# tiller.net
KiCad netlist of a schematic drawn in EAGLE
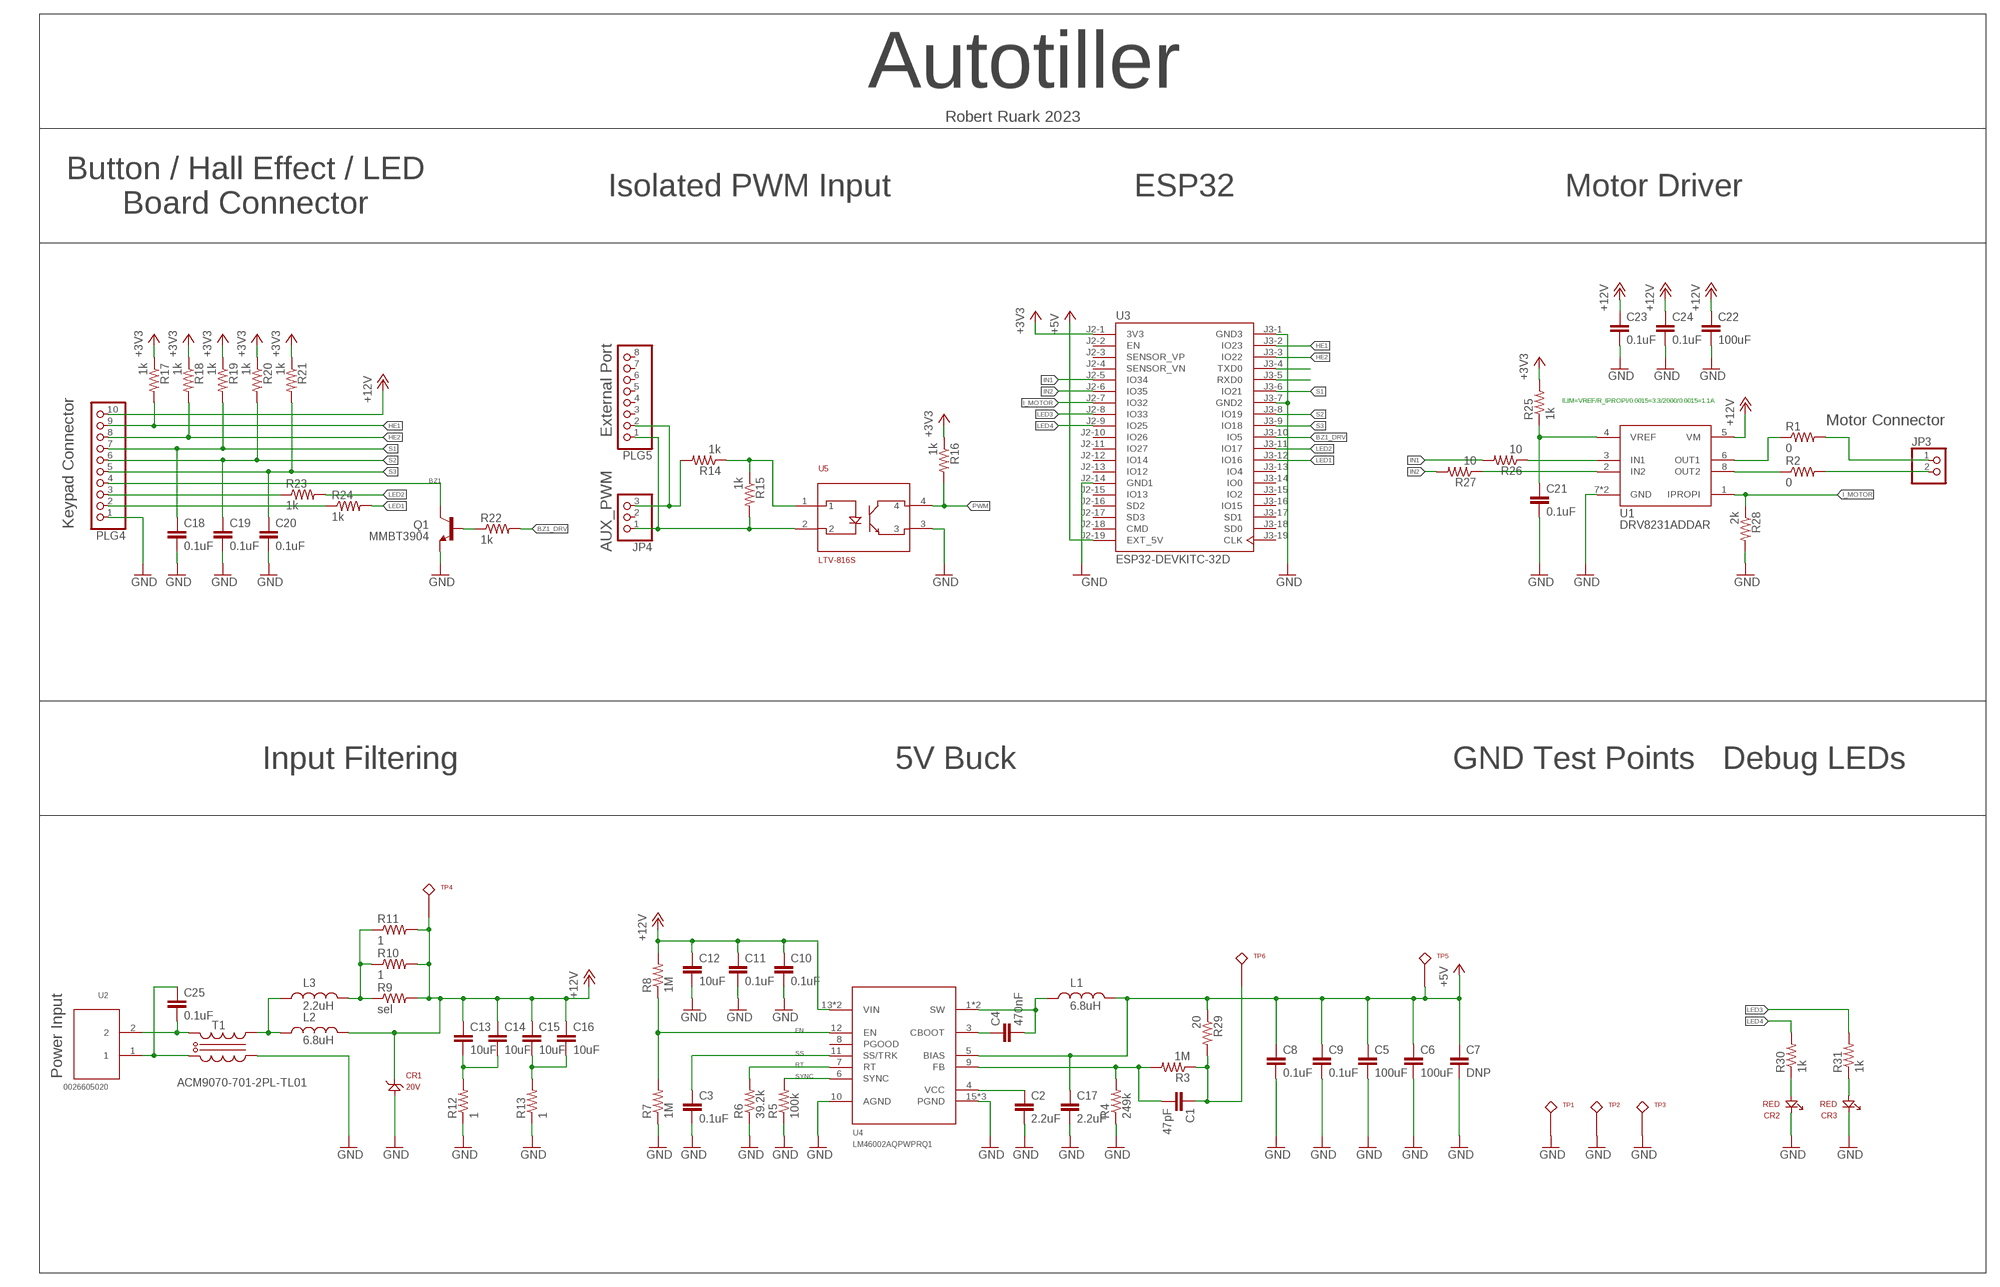
[diagram p0: schematic, sheet 1]

(export (version "E")
  (design (tool "Eeschema 10.0.6"))
  (components
    (comp (ref "C1")
      (value "47pF")
      (footprint "eagle-import:0603")
      (libsource (lib "eagle-import") (part "0603_CAPACITOR"))
    )
    (comp (ref "C2")
      (value "2.2uF")
      (footprint "eagle-import:0805")
      (libsource (lib "eagle-import") (part "0805_CAPACITOR"))
    )
    (comp (ref "C3")
      (value "0.1uF")
      (footprint "eagle-import:0603")
      (libsource (lib "eagle-import") (part "0603_CAPACITOR"))
    )
    (comp (ref "C4")
      (value "470nF")
      (footprint "eagle-import:0805")
      (libsource (lib "eagle-import") (part "0805_CAPACITOR"))
    )
    (comp (ref "C5")
      (value "100uF")
      (footprint "eagle-import:1210")
      (libsource (lib "eagle-import") (part "1210_CAPACITOR"))
    )
    (comp (ref "C6")
      (value "100uF")
      (footprint "eagle-import:1210")
      (libsource (lib "eagle-import") (part "1210_CAPACITOR"))
    )
    (comp (ref "C7")
      (value "DNP")
      (footprint "eagle-import:1210")
      (libsource (lib "eagle-import") (part "1210_CAPACITOR"))
    )
    (comp (ref "C8")
      (value "0.1uF")
      (footprint "eagle-import:0603")
      (libsource (lib "eagle-import") (part "0603_CAPACITOR"))
    )
    (comp (ref "C9")
      (value "0.1uF")
      (footprint "eagle-import:0603")
      (libsource (lib "eagle-import") (part "0603_CAPACITOR"))
    )
    (comp (ref "C10")
      (value "0.1uF")
      (footprint "eagle-import:0603")
      (libsource (lib "eagle-import") (part "0603_CAPACITOR"))
    )
    (comp (ref "C11")
      (value "0.1uF")
      (footprint "eagle-import:0603")
      (libsource (lib "eagle-import") (part "0603_CAPACITOR"))
    )
    (comp (ref "C12")
      (value "10uF")
      (footprint "eagle-import:1210")
      (libsource (lib "eagle-import") (part "1210_CAPACITOR"))
    )
    (comp (ref "C13")
      (value "10uF")
      (footprint "eagle-import:1210")
      (libsource (lib "eagle-import") (part "1210_CAPACITOR"))
    )
    (comp (ref "C14")
      (value "10uF")
      (footprint "eagle-import:1210")
      (libsource (lib "eagle-import") (part "1210_CAPACITOR"))
    )
    (comp (ref "C15")
      (value "10uF")
      (footprint "eagle-import:1210")
      (libsource (lib "eagle-import") (part "1210_CAPACITOR"))
    )
    (comp (ref "C16")
      (value "10uF")
      (footprint "eagle-import:1210")
      (libsource (lib "eagle-import") (part "1210_CAPACITOR"))
    )
    (comp (ref "C17")
      (value "2.2uF")
      (footprint "eagle-import:0805")
      (libsource (lib "eagle-import") (part "0805_CAPACITOR"))
    )
    (comp (ref "C18")
      (value "0.1uF")
      (footprint "eagle-import:0603")
      (libsource (lib "eagle-import") (part "0603_CAPACITOR"))
    )
    (comp (ref "C19")
      (value "0.1uF")
      (footprint "eagle-import:0603")
      (libsource (lib "eagle-import") (part "0603_CAPACITOR"))
    )
    (comp (ref "C20")
      (value "0.1uF")
      (footprint "eagle-import:0603")
      (libsource (lib "eagle-import") (part "0603_CAPACITOR"))
    )
    (comp (ref "C21")
      (value "0.1uF")
      (footprint "eagle-import:0603")
      (libsource (lib "eagle-import") (part "0603_CAPACITOR"))
    )
    (comp (ref "C22")
      (value "100uF")
      (footprint "eagle-import:1210")
      (libsource (lib "eagle-import") (part "1210_CAPACITOR"))
    )
    (comp (ref "C23")
      (value "0.1uF")
      (footprint "eagle-import:0603")
      (libsource (lib "eagle-import") (part "0603_CAPACITOR"))
    )
    (comp (ref "C24")
      (value "0.1uF")
      (footprint "eagle-import:0603")
      (libsource (lib "eagle-import") (part "0603_CAPACITOR"))
    )
    (comp (ref "C25")
      (value "0.1uF")
      (footprint "eagle-import:0603")
      (libsource (lib "eagle-import") (part "0603_CAPACITOR"))
    )
    (comp (ref "CR1")
      (value "20V")
      (footprint "eagle-import:DO-214AC")
      (fields (field (name "PARTNO") "732-SMAJ20ACT-ND"))
      (libsource (lib "eagle-import") (part "SMAJ20A"))
    )
    (comp (ref "CR2")
      (value "RED")
      (footprint "eagle-import:0603_DIODE")
      (fields (field (name "PARTNO") "732-4978-1-ND"))
      (libsource (lib "eagle-import") (part "150060RS75000"))
    )
    (comp (ref "CR3")
      (value "RED")
      (footprint "eagle-import:0603_DIODE")
      (fields (field (name "PARTNO") "732-4978-1-ND"))
      (libsource (lib "eagle-import") (part "150060RS75000"))
    )
    (comp (ref "JP3")
      (value "PINHD-1X2/90")
      (footprint "eagle-import:1X02_90")
      (libsource (lib "eagle-import") (part "PINHD-1X2/90"))
    )
    (comp (ref "JP4")
      (value "PINHD-1X3")
      (footprint "eagle-import:1X03")
      (libsource (lib "eagle-import") (part "PINHD-1X3"))
    )
    (comp (ref "L1")
      (value "6.8uH")
      (footprint "eagle-import:NR6028")
      (fields (field (name "PARTNO") "587-2629-1-ND"))
      (libsource (lib "eagle-import") (part "NR6020T6R8N"))
    )
    (comp (ref "L2")
      (value "6.8uH")
      (footprint "eagle-import:NR6028")
      (fields (field (name "PARTNO") "587-2629-1-ND"))
      (libsource (lib "eagle-import") (part "NR6020T6R8N"))
    )
    (comp (ref "L3")
      (value "2.2uH")
      (footprint "eagle-import:NR6028")
      (fields (field (name "PARTNO") "587-2098-1-ND"))
      (libsource (lib "eagle-import") (part "NR6028T2R2N"))
    )
    (comp (ref "PLG4")
      (value "PINHD-1X10")
      (footprint "eagle-import:1X10")
      (libsource (lib "eagle-import") (part "PINHD-1X10"))
    )
    (comp (ref "PLG5")
      (value "PINHD-1X8")
      (footprint "eagle-import:1X08")
      (libsource (lib "eagle-import") (part "PINHD-1X8"))
    )
    (comp (ref "Q1")
      (value "MMBT3904")
      (footprint "eagle-import:SOT23-3_CENTERED")
      (libsource (lib "eagle-import") (part "MMBT3904-TPCENTERED"))
    )
    (comp (ref "R1")
      (value "0")
      (footprint "eagle-import:1206")
      (libsource (lib "eagle-import") (part "1206_RESISTOR"))
    )
    (comp (ref "R2")
      (value "0")
      (footprint "eagle-import:1206")
      (libsource (lib "eagle-import") (part "1206_RESISTOR"))
    )
    (comp (ref "R3")
      (value "1M")
      (footprint "eagle-import:0603")
      (libsource (lib "eagle-import") (part "0603_RESISTOR"))
    )
    (comp (ref "R4")
      (value "249k")
      (footprint "eagle-import:0603")
      (libsource (lib "eagle-import") (part "0603_RESISTOR"))
    )
    (comp (ref "R5")
      (value "100k")
      (footprint "eagle-import:0603")
      (libsource (lib "eagle-import") (part "0603_RESISTOR"))
    )
    (comp (ref "R6")
      (value "39.2k")
      (footprint "eagle-import:0603")
      (libsource (lib "eagle-import") (part "0603_RESISTOR"))
    )
    (comp (ref "R7")
      (value "1M")
      (footprint "eagle-import:0603")
      (libsource (lib "eagle-import") (part "0603_RESISTOR"))
    )
    (comp (ref "R8")
      (value "1M")
      (footprint "eagle-import:0603")
      (libsource (lib "eagle-import") (part "0603_RESISTOR"))
    )
    (comp (ref "R9")
      (value "sel")
      (footprint "eagle-import:1206")
      (libsource (lib "eagle-import") (part "1206_RESISTOR"))
    )
    (comp (ref "R10")
      (value "1")
      (footprint "eagle-import:1206")
      (libsource (lib "eagle-import") (part "1206_RESISTOR"))
    )
    (comp (ref "R11")
      (value "1")
      (footprint "eagle-import:1206")
      (libsource (lib "eagle-import") (part "1206_RESISTOR"))
    )
    (comp (ref "R12")
      (value "1")
      (footprint "eagle-import:1206")
      (libsource (lib "eagle-import") (part "1206_RESISTOR"))
    )
    (comp (ref "R13")
      (value "1")
      (footprint "eagle-import:1206")
      (libsource (lib "eagle-import") (part "1206_RESISTOR"))
    )
    (comp (ref "R14")
      (value "1k")
      (footprint "eagle-import:0603")
      (libsource (lib "eagle-import") (part "0603_RESISTOR"))
    )
    (comp (ref "R15")
      (value "1k")
      (footprint "eagle-import:0603")
      (libsource (lib "eagle-import") (part "0603_RESISTOR"))
    )
    (comp (ref "R16")
      (value "1k")
      (footprint "eagle-import:0603")
      (libsource (lib "eagle-import") (part "0603_RESISTOR"))
    )
    (comp (ref "R17")
      (value "1k")
      (footprint "eagle-import:0603")
      (libsource (lib "eagle-import") (part "0603_RESISTOR"))
    )
    (comp (ref "R18")
      (value "1k")
      (footprint "eagle-import:0603")
      (libsource (lib "eagle-import") (part "0603_RESISTOR"))
    )
    (comp (ref "R19")
      (value "1k")
      (footprint "eagle-import:0603")
      (libsource (lib "eagle-import") (part "0603_RESISTOR"))
    )
    (comp (ref "R20")
      (value "1k")
      (footprint "eagle-import:0603")
      (libsource (lib "eagle-import") (part "0603_RESISTOR"))
    )
    (comp (ref "R21")
      (value "1k")
      (footprint "eagle-import:0603")
      (libsource (lib "eagle-import") (part "0603_RESISTOR"))
    )
    (comp (ref "R22")
      (value "1k")
      (footprint "eagle-import:0603")
      (libsource (lib "eagle-import") (part "0603_RESISTOR"))
    )
    (comp (ref "R23")
      (value "1k")
      (footprint "eagle-import:0603")
      (libsource (lib "eagle-import") (part "0603_RESISTOR"))
    )
    (comp (ref "R24")
      (value "1k")
      (footprint "eagle-import:0603")
      (libsource (lib "eagle-import") (part "0603_RESISTOR"))
    )
    (comp (ref "R25")
      (value "1k")
      (footprint "eagle-import:0603")
      (libsource (lib "eagle-import") (part "0603_RESISTOR"))
    )
    (comp (ref "R26")
      (value "10")
      (footprint "eagle-import:0603")
      (libsource (lib "eagle-import") (part "0603_RESISTOR"))
    )
    (comp (ref "R27")
      (value "10")
      (footprint "eagle-import:0603")
      (libsource (lib "eagle-import") (part "0603_RESISTOR"))
    )
    (comp (ref "R28")
      (value "2k")
      (footprint "eagle-import:0603")
      (libsource (lib "eagle-import") (part "0603_RESISTOR"))
    )
    (comp (ref "R29")
      (value "20")
      (footprint "eagle-import:0603")
      (libsource (lib "eagle-import") (part "0603_RESISTOR"))
    )
    (comp (ref "R30")
      (value "1k")
      (footprint "eagle-import:0603")
      (libsource (lib "eagle-import") (part "0603_RESISTOR"))
    )
    (comp (ref "R31")
      (value "1k")
      (footprint "eagle-import:0603")
      (libsource (lib "eagle-import") (part "0603_RESISTOR"))
    )
    (comp (ref "T1")
      (value "ACM9070-701-2PL-TL01")
      (footprint "eagle-import:ACM9070")
      (fields (field (name "PARTNO") "445-2216-1-ND"))
      (libsource (lib "eagle-import") (part "ACM9070-701-2PL-TL01"))
    )
    (comp (ref "TP1")
      (value "5011")
      (footprint "eagle-import:5010")
      (fields (field (name "PARTNO") "36-5011-ND"))
      (libsource (lib "eagle-import") (part "5011"))
    )
    (comp (ref "TP2")
      (value "5011")
      (footprint "eagle-import:5010")
      (fields (field (name "PARTNO") "36-5011-ND"))
      (libsource (lib "eagle-import") (part "5011"))
    )
    (comp (ref "TP3")
      (value "5011")
      (footprint "eagle-import:5010")
      (fields (field (name "PARTNO") "36-5011-ND"))
      (libsource (lib "eagle-import") (part "5011"))
    )
    (comp (ref "TP4")
      (value "5010")
      (footprint "eagle-import:5010")
      (fields (field (name "PARTNO") "36-5010-ND"))
      (libsource (lib "eagle-import") (part "5010"))
    )
    (comp (ref "TP5")
      (value "5010")
      (footprint "eagle-import:5010")
      (fields (field (name "PARTNO") "36-5010-ND"))
      (libsource (lib "eagle-import") (part "5010"))
    )
    (comp (ref "TP6")
      (value "5010")
      (footprint "eagle-import:5010")
      (fields (field (name "PARTNO") "36-5010-ND"))
      (libsource (lib "eagle-import") (part "5010"))
    )
    (comp (ref "U1")
      (value "DRV8231ADDAR")
      (footprint "eagle-import:SOIC8_TP")
      (fields (field (name "PARTNO") "296-DRV8231ADDARCT-ND"))
      (libsource (lib "eagle-import") (part "DRV8231ADDAR"))
    )
    (comp (ref "U2")
      (value "0026605020")
      (footprint "eagle-import:3.96MM")
      (fields (field (name "PARTNO") "WM4640-ND"))
      (libsource (lib "eagle-import") (part "0026605020"))
    )
    (comp (ref "U3")
      (value "ESP32-DEVKITC-32D")
      (footprint "eagle-import:MODULE_ESP32-DEVKITC-32D")
      (fields (field (name "MF") "Espressif Systems"))
      (libsource (lib "eagle-import") (part "ESP32-DEVKITC-32D"))
    )
    (comp (ref "U4")
      (value "LM46002AQPWPRQ1")
      (footprint "eagle-import:TSSOP16-POWER")
      (fields (field (name "PARTNO") "296-48923-1-ND"))
      (libsource (lib "eagle-import") (part "LM46002AQPWPRQ1"))
    )
    (comp (ref "U5")
      (value "LTV-816S")
      (footprint "eagle-import:LTV-816S")
      (fields (field (name "PARTNO") "160-1892-1-ND"))
      (libsource (lib "eagle-import") (part "LTV-816S"))
    )
  )
  (nets
    (net (code "1") (name "+3V3") (class "Default")
      (node (ref "R16") (pin "1") (pinfunction "1_1") (pintype "passive"))
      (node (ref "R17") (pin "1") (pinfunction "1_1") (pintype "passive"))
      (node (ref "R18") (pin "1") (pinfunction "1_1") (pintype "passive"))
      (node (ref "R19") (pin "1") (pinfunction "1_1") (pintype "passive"))
      (node (ref "R20") (pin "1") (pinfunction "1_1") (pintype "passive"))
      (node (ref "R21") (pin "1") (pinfunction "1_1") (pintype "passive"))
      (node (ref "R25") (pin "2") (pinfunction "2_2") (pintype "passive"))
      (node (ref "U3") (pin "J2-1") (pinfunction "3V3_J2-1") (pintype "power_in"))
    )
    (net (code "2") (name "+5V") (class "Default")
      (node (ref "C17") (pin "1") (pinfunction "1_1") (pintype "passive"))
      (node (ref "C5") (pin "1") (pinfunction "1_1") (pintype "passive"))
      (node (ref "C6") (pin "1") (pinfunction "1_1") (pintype "passive"))
      (node (ref "C7") (pin "1") (pinfunction "1_1") (pintype "passive"))
      (node (ref "C8") (pin "1") (pinfunction "1_1") (pintype "passive"))
      (node (ref "C9") (pin "1") (pinfunction "1_1") (pintype "passive"))
      (node (ref "L1") (pin "P$2") (pinfunction "P$2_P$2") (pintype "bidirectional"))
      (node (ref "R29") (pin "1") (pinfunction "1_1") (pintype "passive"))
      (node (ref "TP5") (pin "P$1") (pinfunction "P$1_P$1") (pintype "bidirectional"))
      (node (ref "U3") (pin "J2-19") (pinfunction "EXT_5V_J2-19") (pintype "power_in"))
      (node (ref "U4") (pin "5") (pinfunction "BIAS_5") (pintype "bidirectional"))
    )
    (net (code "3") (name "+12V") (class "Default")
      (node (ref "C10") (pin "1") (pinfunction "1_1") (pintype "passive"))
      (node (ref "C11") (pin "1") (pinfunction "1_1") (pintype "passive"))
      (node (ref "C12") (pin "1") (pinfunction "1_1") (pintype "passive"))
      (node (ref "C13") (pin "1") (pinfunction "1_1") (pintype "passive"))
      (node (ref "C14") (pin "1") (pinfunction "1_1") (pintype "passive"))
      (node (ref "C15") (pin "1") (pinfunction "1_1") (pintype "passive"))
      (node (ref "C16") (pin "1") (pinfunction "1_1") (pintype "passive"))
      (node (ref "C22") (pin "1") (pinfunction "1_1") (pintype "passive"))
      (node (ref "C23") (pin "1") (pinfunction "1_1") (pintype "passive"))
      (node (ref "C24") (pin "1") (pinfunction "1_1") (pintype "passive"))
      (node (ref "CR1") (pin "C") (pinfunction "K_C") (pintype "bidirectional"))
      (node (ref "L2") (pin "P$2") (pinfunction "P$2_P$2") (pintype "bidirectional"))
      (node (ref "PLG4") (pin "10") (pinfunction "10_10") (pintype "passive"))
      (node (ref "R10") (pin "2") (pinfunction "2_2") (pintype "passive"))
      (node (ref "R11") (pin "2") (pinfunction "2_2") (pintype "passive"))
      (node (ref "R8") (pin "2") (pinfunction "2_2") (pintype "passive"))
      (node (ref "R9") (pin "2") (pinfunction "2_2") (pintype "passive"))
      (node (ref "TP4") (pin "P$1") (pinfunction "P$1_P$1") (pintype "bidirectional"))
      (node (ref "U1") (pin "5") (pinfunction "VM_5") (pintype "bidirectional"))
      (node (ref "U4") (pin "13") (pinfunction "VIN_13") (pintype "bidirectional"))
      (node (ref "U4") (pin "14") (pinfunction "VIN_14") (pintype "bidirectional"))
    )
    (net (code "4") (name "/BZ1") (class "Default")
      (node (ref "PLG4") (pin "4") (pinfunction "4_4") (pintype "passive"))
      (node (ref "Q1") (pin "3") (pinfunction "C_3") (pintype "passive"))
    )
    (net (code "5") (name "/EN") (class "Default")
      (node (ref "R7") (pin "2") (pinfunction "2_2") (pintype "passive"))
      (node (ref "R8") (pin "1") (pinfunction "1_1") (pintype "passive"))
      (node (ref "U4") (pin "12") (pinfunction "EN_12") (pintype "bidirectional"))
    )
    (net (code "6") (name "/RT") (class "Default")
      (node (ref "R6") (pin "2") (pinfunction "2_2") (pintype "passive"))
      (node (ref "U4") (pin "7") (pinfunction "RT_7") (pintype "bidirectional"))
    )
    (net (code "7") (name "/SS") (class "Default")
      (node (ref "C3") (pin "1") (pinfunction "1_1") (pintype "passive"))
      (node (ref "U4") (pin "11") (pinfunction "SS/TRK_11") (pintype "bidirectional"))
    )
    (net (code "8") (name "/SYNC") (class "Default")
      (node (ref "R5") (pin "2") (pinfunction "2_2") (pintype "passive"))
      (node (ref "U4") (pin "6") (pinfunction "SYNC_6") (pintype "bidirectional"))
    )
    (net (code "9") (name "BZ1_DRV") (class "Default")
      (node (ref "R22") (pin "2") (pinfunction "2_2") (pintype "passive"))
      (node (ref "U3") (pin "J3-10") (pinfunction "IO5_J3-10") (pintype "bidirectional"))
    )
    (net (code "10") (name "GND") (class "Default")
      (node (ref "C10") (pin "2") (pinfunction "2_2") (pintype "passive"))
      (node (ref "C11") (pin "2") (pinfunction "2_2") (pintype "passive"))
      (node (ref "C12") (pin "2") (pinfunction "2_2") (pintype "passive"))
      (node (ref "C17") (pin "2") (pinfunction "2_2") (pintype "passive"))
      (node (ref "C18") (pin "2") (pinfunction "2_2") (pintype "passive"))
      (node (ref "C19") (pin "2") (pinfunction "2_2") (pintype "passive"))
      (node (ref "C2") (pin "2") (pinfunction "2_2") (pintype "passive"))
      (node (ref "C20") (pin "2") (pinfunction "2_2") (pintype "passive"))
      (node (ref "C21") (pin "2") (pinfunction "2_2") (pintype "passive"))
      (node (ref "C22") (pin "2") (pinfunction "2_2") (pintype "passive"))
      (node (ref "C23") (pin "2") (pinfunction "2_2") (pintype "passive"))
      (node (ref "C24") (pin "2") (pinfunction "2_2") (pintype "passive"))
      (node (ref "C3") (pin "2") (pinfunction "2_2") (pintype "passive"))
      (node (ref "C5") (pin "2") (pinfunction "2_2") (pintype "passive"))
      (node (ref "C6") (pin "2") (pinfunction "2_2") (pintype "passive"))
      (node (ref "C7") (pin "2") (pinfunction "2_2") (pintype "passive"))
      (node (ref "C8") (pin "2") (pinfunction "2_2") (pintype "passive"))
      (node (ref "C9") (pin "2") (pinfunction "2_2") (pintype "passive"))
      (node (ref "CR1") (pin "A") (pinfunction "A_A") (pintype "bidirectional"))
      (node (ref "CR2") (pin "K") (pinfunction "K_K") (pintype "bidirectional"))
      (node (ref "CR3") (pin "K") (pinfunction "K_K") (pintype "bidirectional"))
      (node (ref "PLG4") (pin "1") (pinfunction "1_1") (pintype "passive"))
      (node (ref "Q1") (pin "2") (pinfunction "E_2") (pintype "passive"))
      (node (ref "R12") (pin "1") (pinfunction "1_1") (pintype "passive"))
      (node (ref "R13") (pin "1") (pinfunction "1_1") (pintype "passive"))
      (node (ref "R28") (pin "2") (pinfunction "2_2") (pintype "passive"))
      (node (ref "R4") (pin "1") (pinfunction "1_1") (pintype "passive"))
      (node (ref "R5") (pin "1") (pinfunction "1_1") (pintype "passive"))
      (node (ref "R6") (pin "1") (pinfunction "1_1") (pintype "passive"))
      (node (ref "R7") (pin "1") (pinfunction "1_1") (pintype "passive"))
      (node (ref "T1") (pin "1OUT") (pinfunction "1OUT_1OUT") (pintype "bidirectional"))
      (node (ref "TP1") (pin "P$1") (pinfunction "P$1_P$1") (pintype "bidirectional"))
      (node (ref "TP2") (pin "P$1") (pinfunction "P$1_P$1") (pintype "bidirectional"))
      (node (ref "TP3") (pin "P$1") (pinfunction "P$1_P$1") (pintype "bidirectional"))
      (node (ref "U1") (pin "7") (pinfunction "GND_7") (pintype "bidirectional"))
      (node (ref "U1") (pin "TP") (pinfunction "GND_TP") (pintype "bidirectional"))
      (node (ref "U3") (pin "J2-14") (pinfunction "GND1_J2-14") (pintype "power_in"))
      (node (ref "U3") (pin "J3-1") (pinfunction "GND3_J3-1") (pintype "power_in"))
      (node (ref "U3") (pin "J3-7") (pinfunction "GND2_J3-7") (pintype "power_in"))
      (node (ref "U4") (pin "10") (pinfunction "AGND_10") (pintype "bidirectional"))
      (node (ref "U4") (pin "15") (pinfunction "PGND_15") (pintype "bidirectional"))
      (node (ref "U4") (pin "16") (pinfunction "PGND_16") (pintype "bidirectional"))
      (node (ref "U4") (pin "P$1") (pinfunction "PGND_P$1") (pintype "bidirectional"))
      (node (ref "U5") (pin "3") (pinfunction "3_3") (pintype "bidirectional"))
    )
    (net (code "11") (name "HE1") (class "Default")
      (node (ref "PLG4") (pin "9") (pinfunction "9_9") (pintype "passive"))
      (node (ref "R17") (pin "2") (pinfunction "2_2") (pintype "passive"))
      (node (ref "U3") (pin "J3-2") (pinfunction "IO23_J3-2") (pintype "bidirectional"))
    )
    (net (code "12") (name "HE2") (class "Default")
      (node (ref "PLG4") (pin "8") (pinfunction "8_8") (pintype "passive"))
      (node (ref "R18") (pin "2") (pinfunction "2_2") (pintype "passive"))
      (node (ref "U3") (pin "J3-3") (pinfunction "IO22_J3-3") (pintype "bidirectional"))
    )
    (net (code "13") (name "IN1") (class "Default")
      (node (ref "R26") (pin "2") (pinfunction "2_2") (pintype "passive"))
      (node (ref "U3") (pin "J2-5") (pinfunction "IO34_J2-5") (pintype "bidirectional"))
    )
    (net (code "14") (name "IN2") (class "Default")
      (node (ref "R27") (pin "2") (pinfunction "2_2") (pintype "passive"))
      (node (ref "U3") (pin "J2-6") (pinfunction "IO35_J2-6") (pintype "bidirectional"))
    )
    (net (code "15") (name "I_MOTOR") (class "Default")
      (node (ref "R28") (pin "1") (pinfunction "1_1") (pintype "passive"))
      (node (ref "U1") (pin "1") (pinfunction "IPROPI_1") (pintype "bidirectional"))
      (node (ref "U3") (pin "J2-7") (pinfunction "IO32_J2-7") (pintype "bidirectional"))
    )
    (net (code "16") (name "LED1") (class "Default")
      (node (ref "R24") (pin "2") (pinfunction "2_2") (pintype "passive"))
      (node (ref "U3") (pin "J3-12") (pinfunction "IO16_J3-12") (pintype "bidirectional"))
    )
    (net (code "17") (name "LED2") (class "Default")
      (node (ref "R23") (pin "2") (pinfunction "2_2") (pintype "passive"))
      (node (ref "U3") (pin "J3-11") (pinfunction "IO17_J3-11") (pintype "bidirectional"))
    )
    (net (code "18") (name "LED3") (class "Default")
      (node (ref "R31") (pin "2") (pinfunction "2_2") (pintype "passive"))
      (node (ref "U3") (pin "J2-8") (pinfunction "IO33_J2-8") (pintype "bidirectional"))
    )
    (net (code "19") (name "LED4") (class "Default")
      (node (ref "R30") (pin "2") (pinfunction "2_2") (pintype "passive"))
      (node (ref "U3") (pin "J2-9") (pinfunction "IO25_J2-9") (pintype "bidirectional"))
    )
    (net (code "20") (name "Net-(C1-Pad1)") (class "Default")
      (node (ref "C1") (pin "1") (pinfunction "1_1") (pintype "passive"))
      (node (ref "R29") (pin "2") (pinfunction "2_2") (pintype "passive"))
      (node (ref "R3") (pin "1") (pinfunction "1_1") (pintype "passive"))
      (node (ref "TP6") (pin "P$1") (pinfunction "P$1_P$1") (pintype "bidirectional"))
    )
    (net (code "21") (name "Net-(C4-Pad2)") (class "Default")
      (node (ref "C4") (pin "2") (pinfunction "2_2") (pintype "passive"))
      (node (ref "L1") (pin "P$1") (pinfunction "P$1_P$1") (pintype "bidirectional"))
      (node (ref "U4") (pin "1") (pinfunction "SW_1") (pintype "bidirectional"))
      (node (ref "U4") (pin "2") (pinfunction "SW_2") (pintype "bidirectional"))
    )
    (net (code "22") (name "Net-(C13-Pad2)") (class "Default")
      (node (ref "C13") (pin "2") (pinfunction "2_2") (pintype "passive"))
      (node (ref "C14") (pin "2") (pinfunction "2_2") (pintype "passive"))
      (node (ref "R12") (pin "2") (pinfunction "2_2") (pintype "passive"))
    )
    (net (code "23") (name "Net-(C15-Pad2)") (class "Default")
      (node (ref "C15") (pin "2") (pinfunction "2_2") (pintype "passive"))
      (node (ref "C16") (pin "2") (pinfunction "2_2") (pintype "passive"))
      (node (ref "R13") (pin "2") (pinfunction "2_2") (pintype "passive"))
    )
    (net (code "24") (name "Net-(C25-Pad1)") (class "Default")
      (node (ref "C25") (pin "1") (pinfunction "1_1") (pintype "passive"))
      (node (ref "T1") (pin "1IN") (pinfunction "1IN_1IN") (pintype "bidirectional"))
      (node (ref "U2") (pin "1") (pinfunction "1_1") (pintype "bidirectional"))
    )
    (net (code "25") (name "Net-(C25-Pad2)") (class "Default")
      (node (ref "C25") (pin "2") (pinfunction "2_2") (pintype "passive"))
      (node (ref "T1") (pin "2IN") (pinfunction "2IN_2IN") (pintype "bidirectional"))
      (node (ref "U2") (pin "2") (pinfunction "2_2") (pintype "bidirectional"))
    )
    (net (code "26") (name "Net-(CR2-PadA)") (class "Default")
      (node (ref "CR2") (pin "A") (pinfunction "A_A") (pintype "bidirectional"))
      (node (ref "R30") (pin "1") (pinfunction "1_1") (pintype "passive"))
    )
    (net (code "27") (name "Net-(CR3-PadA)") (class "Default")
      (node (ref "CR3") (pin "A") (pinfunction "A_A") (pintype "bidirectional"))
      (node (ref "R31") (pin "1") (pinfunction "1_1") (pintype "passive"))
    )
    (net (code "28") (name "Net-(JP3-Pad1)") (class "Default")
      (node (ref "JP3") (pin "1") (pinfunction "1_1") (pintype "passive"))
      (node (ref "R1") (pin "2") (pinfunction "2_2") (pintype "passive"))
    )
    (net (code "29") (name "Net-(JP3-Pad2)") (class "Default")
      (node (ref "JP3") (pin "2") (pinfunction "2_2") (pintype "passive"))
      (node (ref "R2") (pin "2") (pinfunction "2_2") (pintype "passive"))
    )
    (net (code "30") (name "Net-(JP4-Pad1)") (class "Default")
      (node (ref "JP4") (pin "1") (pinfunction "1_1") (pintype "passive"))
      (node (ref "PLG5") (pin "1") (pinfunction "1_1") (pintype "passive"))
      (node (ref "R15") (pin "2") (pinfunction "2_2") (pintype "passive"))
      (node (ref "U5") (pin "2") (pinfunction "2_2") (pintype "bidirectional"))
    )
    (net (code "31") (name "Net-(JP4-Pad3)") (class "Default")
      (node (ref "JP4") (pin "3") (pinfunction "3_3") (pintype "passive"))
      (node (ref "PLG5") (pin "2") (pinfunction "2_2") (pintype "passive"))
      (node (ref "R14") (pin "2") (pinfunction "2_2") (pintype "passive"))
    )
    (net (code "32") (name "Net-(L2-PadP$1)") (class "Default")
      (node (ref "L2") (pin "P$1") (pinfunction "P$1_P$1") (pintype "bidirectional"))
      (node (ref "L3") (pin "P$1") (pinfunction "P$1_P$1") (pintype "bidirectional"))
      (node (ref "T1") (pin "2OUT") (pinfunction "2OUT_2OUT") (pintype "bidirectional"))
    )
    (net (code "33") (name "Net-(L3-PadP$2)") (class "Default")
      (node (ref "L3") (pin "P$2") (pinfunction "P$2_P$2") (pintype "bidirectional"))
      (node (ref "R10") (pin "1") (pinfunction "1_1") (pintype "passive"))
      (node (ref "R11") (pin "1") (pinfunction "1_1") (pintype "passive"))
      (node (ref "R9") (pin "1") (pinfunction "1_1") (pintype "passive"))
    )
    (net (code "34") (name "Net-(PLG4-Pad2)") (class "Default")
      (node (ref "PLG4") (pin "2") (pinfunction "2_2") (pintype "passive"))
      (node (ref "R24") (pin "1") (pinfunction "1_1") (pintype "passive"))
    )
    (net (code "35") (name "Net-(PLG4-Pad3)") (class "Default")
      (node (ref "PLG4") (pin "3") (pinfunction "3_3") (pintype "passive"))
      (node (ref "R23") (pin "1") (pinfunction "1_1") (pintype "passive"))
    )
    (net (code "36") (name "Net-(Q1-B)") (class "Default")
      (node (ref "Q1") (pin "1") (pinfunction "B_1") (pintype "passive"))
      (node (ref "R22") (pin "1") (pinfunction "1_1") (pintype "passive"))
    )
    (net (code "37") (name "Net-(R14-Pad1)") (class "Default")
      (node (ref "R14") (pin "1") (pinfunction "1_1") (pintype "passive"))
      (node (ref "R15") (pin "1") (pinfunction "1_1") (pintype "passive"))
      (node (ref "U5") (pin "1") (pinfunction "1_1") (pintype "bidirectional"))
    )
    (net (code "38") (name "Net-(U1-IN1)") (class "Default")
      (node (ref "R26") (pin "1") (pinfunction "1_1") (pintype "passive"))
      (node (ref "U1") (pin "3") (pinfunction "IN1_3") (pintype "bidirectional"))
    )
    (net (code "39") (name "Net-(U1-IN2)") (class "Default")
      (node (ref "R27") (pin "1") (pinfunction "1_1") (pintype "passive"))
      (node (ref "U1") (pin "2") (pinfunction "IN2_2") (pintype "bidirectional"))
    )
    (net (code "40") (name "Net-(U1-OUT1)") (class "Default")
      (node (ref "R1") (pin "1") (pinfunction "1_1") (pintype "passive"))
      (node (ref "U1") (pin "6") (pinfunction "OUT1_6") (pintype "bidirectional"))
    )
    (net (code "41") (name "Net-(U1-OUT2)") (class "Default")
      (node (ref "R2") (pin "1") (pinfunction "1_1") (pintype "passive"))
      (node (ref "U1") (pin "8") (pinfunction "OUT2_8") (pintype "bidirectional"))
    )
    (net (code "42") (name "Net-(U1-VREF)") (class "Default")
      (node (ref "C21") (pin "1") (pinfunction "1_1") (pintype "passive"))
      (node (ref "R25") (pin "1") (pinfunction "1_1") (pintype "passive"))
      (node (ref "U1") (pin "4") (pinfunction "VREF_4") (pintype "bidirectional"))
    )
    (net (code "43") (name "Net-(U4-CBOOT)") (class "Default")
      (node (ref "C4") (pin "1") (pinfunction "1_1") (pintype "passive"))
      (node (ref "U4") (pin "3") (pinfunction "CBOOT_3") (pintype "bidirectional"))
    )
    (net (code "44") (name "Net-(U4-FB)") (class "Default")
      (node (ref "C1") (pin "2") (pinfunction "2_2") (pintype "passive"))
      (node (ref "R3") (pin "2") (pinfunction "2_2") (pintype "passive"))
      (node (ref "R4") (pin "2") (pinfunction "2_2") (pintype "passive"))
      (node (ref "U4") (pin "9") (pinfunction "FB_9") (pintype "bidirectional"))
    )
    (net (code "45") (name "Net-(U4-VCC)") (class "Default")
      (node (ref "C2") (pin "1") (pinfunction "1_1") (pintype "passive"))
      (node (ref "U4") (pin "4") (pinfunction "VCC_4") (pintype "bidirectional"))
    )
    (net (code "46") (name "PWM") (class "Default")
      (node (ref "R16") (pin "2") (pinfunction "2_2") (pintype "passive"))
      (node (ref "U5") (pin "4") (pinfunction "4_4") (pintype "bidirectional"))
    )
    (net (code "47") (name "S1") (class "Default")
      (node (ref "C18") (pin "1") (pinfunction "1_1") (pintype "passive"))
      (node (ref "PLG4") (pin "7") (pinfunction "7_7") (pintype "passive"))
      (node (ref "R19") (pin "2") (pinfunction "2_2") (pintype "passive"))
      (node (ref "U3") (pin "J3-6") (pinfunction "IO21_J3-6") (pintype "bidirectional"))
    )
    (net (code "48") (name "S2") (class "Default")
      (node (ref "C19") (pin "1") (pinfunction "1_1") (pintype "passive"))
      (node (ref "PLG4") (pin "6") (pinfunction "6_6") (pintype "passive"))
      (node (ref "R20") (pin "2") (pinfunction "2_2") (pintype "passive"))
      (node (ref "U3") (pin "J3-8") (pinfunction "IO19_J3-8") (pintype "bidirectional"))
    )
    (net (code "49") (name "S3") (class "Default")
      (node (ref "C20") (pin "1") (pinfunction "1_1") (pintype "passive"))
      (node (ref "PLG4") (pin "5") (pinfunction "5_5") (pintype "passive"))
      (node (ref "R21") (pin "2") (pinfunction "2_2") (pintype "passive"))
      (node (ref "U3") (pin "J3-9") (pinfunction "IO18_J3-9") (pintype "bidirectional"))
    )
    (net (code "50") (name "unconnected-(JP4-Pad2)") (class "Default")
      (node (ref "JP4") (pin "2") (pinfunction "2_2") (pintype "passive"))
    )
    (net (code "51") (name "unconnected-(PLG5-Pad3)") (class "Default")
      (node (ref "PLG5") (pin "3") (pinfunction "3_3") (pintype "passive"))
    )
    (net (code "52") (name "unconnected-(PLG5-Pad4)") (class "Default")
      (node (ref "PLG5") (pin "4") (pinfunction "4_4") (pintype "passive"))
    )
    (net (code "53") (name "unconnected-(PLG5-Pad5)") (class "Default")
      (node (ref "PLG5") (pin "5") (pinfunction "5_5") (pintype "passive"))
    )
    (net (code "54") (name "unconnected-(PLG5-Pad6)") (class "Default")
      (node (ref "PLG5") (pin "6") (pinfunction "6_6") (pintype "passive"))
    )
    (net (code "55") (name "unconnected-(PLG5-Pad7)") (class "Default")
      (node (ref "PLG5") (pin "7") (pinfunction "7_7") (pintype "passive"))
    )
    (net (code "56") (name "unconnected-(PLG5-Pad8)") (class "Default")
      (node (ref "PLG5") (pin "8") (pinfunction "8_8") (pintype "passive"))
    )
    (net (code "57") (name "unconnected-(U3-CLK-PadJ3-19)") (class "Default")
      (node (ref "U3") (pin "J3-19") (pinfunction "CLK_J3-19") (pintype "input"))
    )
    (net (code "58") (name "unconnected-(U3-CMD-PadJ2-18)") (class "Default")
      (node (ref "U3") (pin "J2-18") (pinfunction "CMD_J2-18") (pintype "bidirectional"))
    )
    (net (code "59") (name "unconnected-(U3-EN-PadJ2-2)") (class "Default")
      (node (ref "U3") (pin "J2-2") (pinfunction "EN_J2-2") (pintype "input"))
    )
    (net (code "60") (name "unconnected-(U3-IO0-PadJ3-14)") (class "Default")
      (node (ref "U3") (pin "J3-14") (pinfunction "IO0_J3-14") (pintype "bidirectional"))
    )
    (net (code "61") (name "unconnected-(U3-IO2-PadJ3-15)") (class "Default")
      (node (ref "U3") (pin "J3-15") (pinfunction "IO2_J3-15") (pintype "bidirectional"))
    )
    (net (code "62") (name "unconnected-(U3-IO4-PadJ3-13)") (class "Default")
      (node (ref "U3") (pin "J3-13") (pinfunction "IO4_J3-13") (pintype "bidirectional"))
    )
    (net (code "63") (name "unconnected-(U3-IO12-PadJ2-13)") (class "Default")
      (node (ref "U3") (pin "J2-13") (pinfunction "IO12_J2-13") (pintype "bidirectional"))
    )
    (net (code "64") (name "unconnected-(U3-IO13-PadJ2-15)") (class "Default")
      (node (ref "U3") (pin "J2-15") (pinfunction "IO13_J2-15") (pintype "bidirectional"))
    )
    (net (code "65") (name "unconnected-(U3-IO14-PadJ2-12)") (class "Default")
      (node (ref "U3") (pin "J2-12") (pinfunction "IO14_J2-12") (pintype "bidirectional"))
    )
    (net (code "66") (name "unconnected-(U3-IO15-PadJ3-16)") (class "Default")
      (node (ref "U3") (pin "J3-16") (pinfunction "IO15_J3-16") (pintype "bidirectional"))
    )
    (net (code "67") (name "unconnected-(U3-IO26-PadJ2-10)") (class "Default")
      (node (ref "U3") (pin "J2-10") (pinfunction "IO26_J2-10") (pintype "bidirectional"))
    )
    (net (code "68") (name "unconnected-(U3-IO27-PadJ2-11)") (class "Default")
      (node (ref "U3") (pin "J2-11") (pinfunction "IO27_J2-11") (pintype "bidirectional"))
    )
    (net (code "69") (name "unconnected-(U3-RXD0-PadJ3-5)") (class "Default")
      (node (ref "U3") (pin "J3-5") (pinfunction "RXD0_J3-5") (pintype "input"))
    )
    (net (code "70") (name "unconnected-(U3-SD0-PadJ3-18)") (class "Default")
      (node (ref "U3") (pin "J3-18") (pinfunction "SD0_J3-18") (pintype "bidirectional"))
    )
    (net (code "71") (name "unconnected-(U3-SD1-PadJ3-17)") (class "Default")
      (node (ref "U3") (pin "J3-17") (pinfunction "SD1_J3-17") (pintype "bidirectional"))
    )
    (net (code "72") (name "unconnected-(U3-SD2-PadJ2-16)") (class "Default")
      (node (ref "U3") (pin "J2-16") (pinfunction "SD2_J2-16") (pintype "bidirectional"))
    )
    (net (code "73") (name "unconnected-(U3-SD3-PadJ2-17)") (class "Default")
      (node (ref "U3") (pin "J2-17") (pinfunction "SD3_J2-17") (pintype "bidirectional"))
    )
    (net (code "74") (name "unconnected-(U3-SENSOR_VN-PadJ2-4)") (class "Default")
      (node (ref "U3") (pin "J2-4") (pinfunction "SENSOR_VN_J2-4") (pintype "input"))
    )
    (net (code "75") (name "unconnected-(U3-SENSOR_VP-PadJ2-3)") (class "Default")
      (node (ref "U3") (pin "J2-3") (pinfunction "SENSOR_VP_J2-3") (pintype "input"))
    )
    (net (code "76") (name "unconnected-(U3-TXD0-PadJ3-4)") (class "Default")
      (node (ref "U3") (pin "J3-4") (pinfunction "TXD0_J3-4") (pintype "output"))
    )
    (net (code "77") (name "unconnected-(U4-PGOOD-Pad8)") (class "Default")
      (node (ref "U4") (pin "8") (pinfunction "PGOOD_8") (pintype "bidirectional"))
    )
  )
)
